# microPower1.net
KiCad netlist of a schematic drawn in Altium Designer
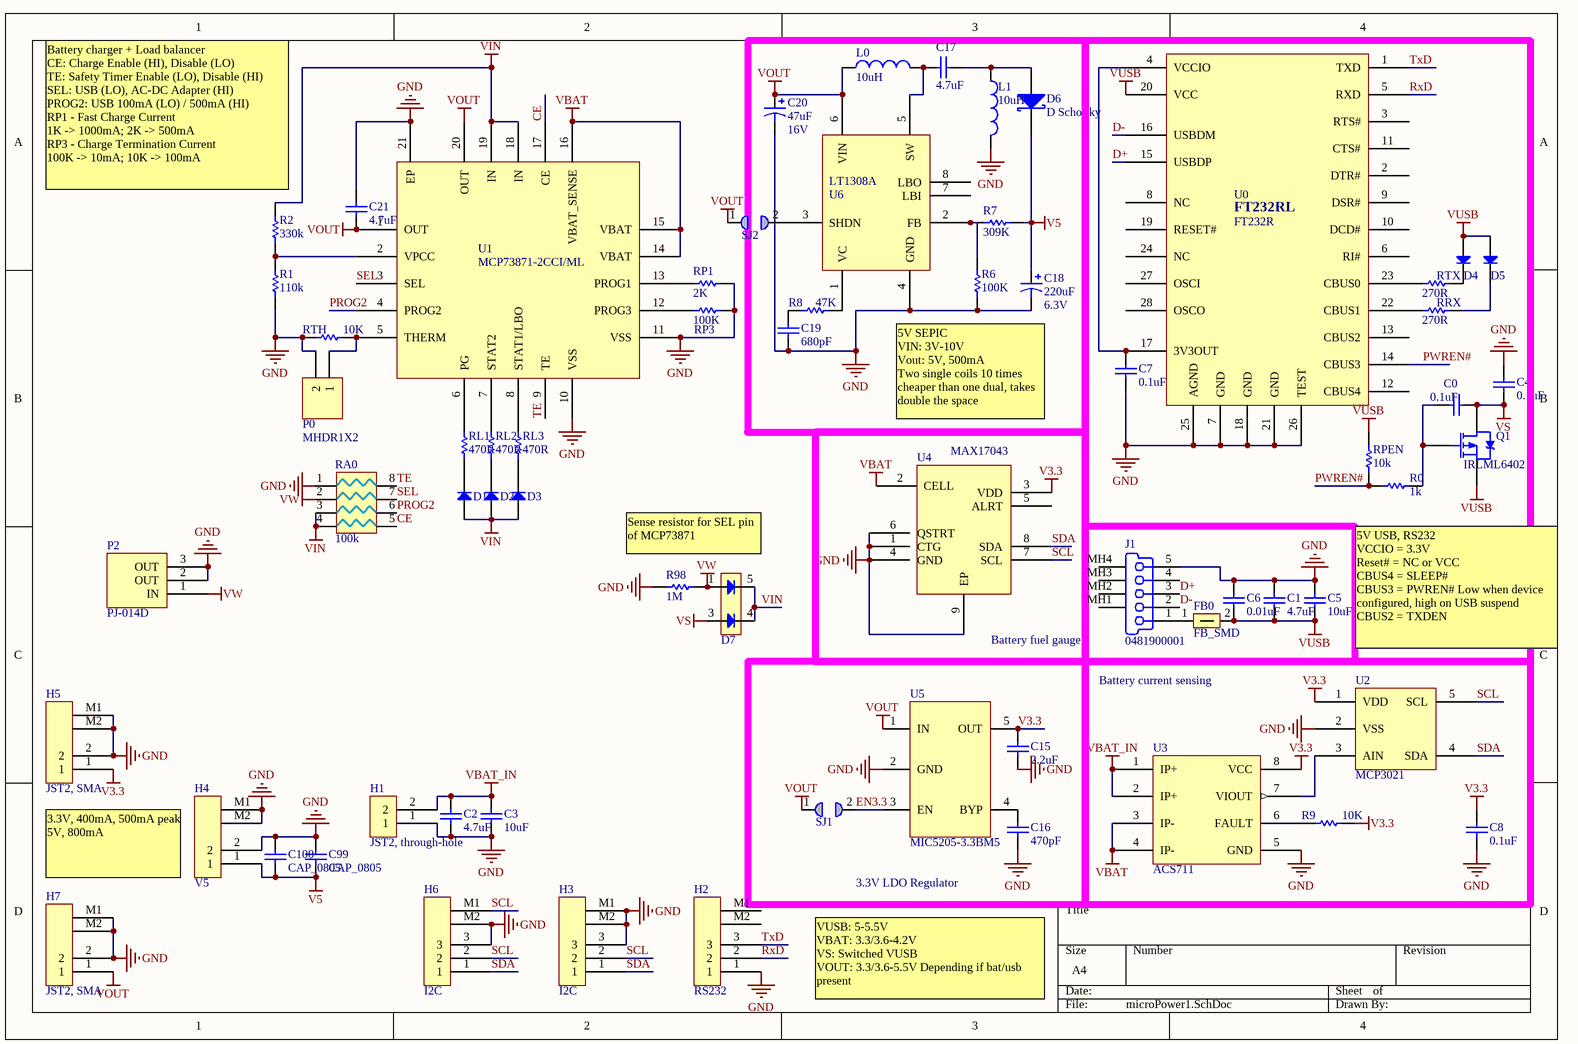
[diagram p0: microPower1.SchDoc]

(export (version "E")
  (design (tool "Eeschema 10.0.6"))
  (components
    (comp (ref "C0")
      (value "0.1uF")
      (footprint "0603_CAP")
      (description "CAP_0603")
      (libsource (lib "ailabLib") (part "CAP_SMD"))
    )
    (comp (ref "C1")
      (value "4.7uF")
      (footprint "0805_CAP")
      (description "Chip Capacitor")
      (libsource (lib "ailabLib") (part "CAP_SMD"))
    )
    (comp (ref "C2")
      (value "4.7uF")
      (footprint "0805_CAP")
      (description "Chip Capacitor")
      (libsource (lib "ailabLib") (part "CAP_SMD"))
    )
    (comp (ref "C3")
      (value "10uF")
      (footprint "0805_CAP")
      (description "Chip Capacitor")
      (libsource (lib "ailabLib") (part "CAP_SMD"))
    )
    (comp (ref "C4")
      (value "0.1uF")
      (footprint "0603_CAP")
      (description "CAP_0603")
      (libsource (lib "ailabLib") (part "CAP_SMD"))
    )
    (comp (ref "C5")
      (value "10uF")
      (footprint "0805_CAP")
      (description "Chip Capacitor")
      (libsource (lib "ailabLib") (part "CAP_SMD"))
    )
    (comp (ref "C6")
      (value "0.01uF")
      (footprint "0603_CAP")
      (description "CAP_0603")
      (libsource (lib "ailabLib") (part "CAP_SMD"))
    )
    (comp (ref "C7")
      (value "0.1uF")
      (footprint "0603_CAP")
      (description "CAP_0603")
      (libsource (lib "ailabLib") (part "CAP_SMD"))
    )
    (comp (ref "C8")
      (value "0.1uF")
      (footprint "0603_CAP")
      (description "CAP_0603")
      (libsource (lib "ailabLib") (part "CAP_SMD"))
    )
    (comp (ref "C15")
      (value "2.2uF")
      (footprint "0603_CAP")
      (description "CAP_0603")
      (libsource (lib "ailabLib") (part "CAP_SMD"))
    )
    (comp (ref "C16")
      (value "470pF")
      (footprint "0603_CAP")
      (description "CAP_0603")
      (libsource (lib "ailabLib") (part "CAP_SMD"))
    )
    (comp (ref "C17")
      (value "4.7uF")
      (footprint "0805_CAP")
      (description "Chip Capacitor")
      (libsource (lib "ailabLib") (part "CAP_SMD"))
    )
    (comp (ref "C18")
      (value "220uF")
      (footprint "CAPMP3528X21N")
      (description "CAP TANT 220UF 6.3V 20% 1411")
      (fields (field (name "VOLTAGE") "6.3V"))
      (libsource (lib "ailabLib") (part "T520B227M006ATE070"))
    )
    (comp (ref "C19")
      (value "680pF")
      (footprint "0603_CAP")
      (description "CAP_0603")
      (libsource (lib "ailabLib") (part "CAP_SMD"))
    )
    (comp (ref "C20")
      (value "47uF")
      (footprint "CAPMP6032X28N")
      (description "CAP TANT 47UF 16V 10% 2312")
      (fields (field (name "VOLTAGE") "16V"))
      (libsource (lib "ailabLib") (part "TR3C476K016C0300"))
    )
    (comp (ref "C21")
      (value "4.7uF")
      (footprint "0805_CAP")
      (description "Chip Capacitor")
      (libsource (lib "ailabLib") (part "CAP_SMD"))
    )
    (comp (ref "C99")
      (value "CAP_0805")
      (footprint "CAP_0805")
      (libsource (lib "ailabLib") (part "CAP_0805"))
    )
    (comp (ref "C100")
      (value "CAP_0805")
      (footprint "CAP_0805")
      (libsource (lib "ailabLib") (part "CAP_0805"))
    )
    (comp (ref "D1") (value "~") (footprint "0603_LED") (libsource (lib "ailabLib") (part "LED_SMD")))
    (comp (ref "D2") (value "~") (footprint "0603_LED") (libsource (lib "ailabLib") (part "LED_SMD")))
    (comp (ref "D3") (value "~") (footprint "0603_LED") (libsource (lib "ailabLib") (part "LED_SMD")))
    (comp (ref "D4") (value "~") (footprint "0603_LED") (libsource (lib "ailabLib") (part "LED_SMD")))
    (comp (ref "D5") (value "~") (footprint "0603_LED") (libsource (lib "ailabLib") (part "LED_SMD")))
    (comp (ref "D6")
      (value "D Schottky")
      (footprint "SMB")
      (description "Schottky Diode")
      (fields (field (name "PUBLISHER") "Altium Limited"))
      (libsource (lib "Miscellaneous Devices") (part "D Schottky"))
    )
    (comp (ref "D7")
      (value "RB496EA")
      (footprint "SOT23-5")
      (description "Schottky barrier diode, 400mV @ 1A")
      (libsource (lib "ailabLib") (part "RB496EA"))
    )
    (comp (ref "FB0") (value "FB_SMD") (footprint "0603_IND") (libsource (lib "ailabLib") (part "FB_SMD")))
    (comp (ref "H1")
      (value "JST2, through-hole")
      (footprint "JST B2B-PH-KL")
      (libsource (lib "ailabLib") (part "JST2, through-hole"))
    )
    (comp (ref "H2")
      (value "RS232")
      (footprint "JST SHR-3V-S")
      (libsource (lib "ailabLib") (part "JST3, SMA"))
    )
    (comp (ref "H3") (value "I2C") (footprint "JST SHR-3V-S") (libsource (lib "ailabLib") (part "JST3, SMA")))
    (comp (ref "H4") (value "V5") (footprint "JST SHR-2V-S") (libsource (lib "ailabLib") (part "JST2, SMA")))
    (comp (ref "H5")
      (value "JST2, SMA")
      (footprint "JST SHR-2V-S")
      (libsource (lib "ailabLib") (part "JST2, SMA"))
    )
    (comp (ref "H6") (value "I2C") (footprint "JST SHR-3V-S") (libsource (lib "ailabLib") (part "JST3, SMA")))
    (comp (ref "H7")
      (value "JST2, SMA")
      (footprint "JST SHR-2V-S")
      (libsource (lib "ailabLib") (part "JST2, SMA"))
    )
    (comp (ref "J1")
      (value "0481900001")
      (footprint "481900001")
      (fields (field (name "PUBLISHER") "Altium Limited"))
      (libsource (lib "ailabLib") (part "0481900001"))
    )
    (comp (ref "L0")
      (value "10uH")
      (footprint "INDP6060X45L")
      (description "INDUCTOR 10UH 3A 20% SMD")
      (libsource (lib "ailabLib") (part "NR6045T100M"))
    )
    (comp (ref "L1")
      (value "10uH")
      (footprint "INDP6060X45L")
      (description "INDUCTOR 10UH 3A 20% SMD")
      (libsource (lib "ailabLib") (part "NR6045T100M"))
    )
    (comp (ref "P0")
      (value "MHDR1X2")
      (footprint "MHDR1X2")
      (description "Header, 2-Pin")
      (fields (field (name "PUBLISHER") "Altium Limited"))
      (libsource (lib "Miscellaneous Connectors") (part "MHDR1X2"))
    )
    (comp (ref "P2")
      (value "PJ-014D")
      (footprint "PJ-014D")
      (description "Power jack, 4.2mm OD, 1.3mm ID, through-hole")
      (libsource (lib "ailabLib") (part "PJ-014D"))
    )
    (comp (ref "Q1")
      (value "IRLML6402")
      (footprint "Micro3_N")
      (description "HEXFET Power MOSFET")
      (fields (field (name "PUBLISHER") "Altium Limited"))
      (libsource (lib "IR Discrete MOSFET - Power") (part "IRLML6401"))
    )
    (comp (ref "R0") (value "1k") (footprint "0603_RES") (libsource (lib "ailabLib") (part "RES_SMD")))
    (comp (ref "R1") (value "110k") (footprint "0603_RES") (libsource (lib "ailabLib") (part "RES_SMD")))
    (comp (ref "R2") (value "330k") (footprint "0603_RES") (libsource (lib "ailabLib") (part "RES_SMD")))
    (comp (ref "R6") (value "100K") (footprint "0603_RES") (libsource (lib "ailabLib") (part "RES_SMD")))
    (comp (ref "R7") (value "309K") (footprint "0603_RES") (libsource (lib "ailabLib") (part "RES_SMD")))
    (comp (ref "R8") (value "47K") (footprint "0603_RES") (libsource (lib "ailabLib") (part "RES_SMD")))
    (comp (ref "R9") (value "10K") (footprint "0603_RES") (libsource (lib "ailabLib") (part "RES_SMD")))
    (comp (ref "R98") (value "1M") (footprint "0603_RES") (libsource (lib "ailabLib") (part "RES_SMD")))
    (comp (ref "RA0")
      (value "100k")
      (footprint "RESCAXS80P320X150X60-8N")
      (description "Resistor array, 4-Way, SMD")
      (libsource (lib "ailabLib") (part "RES_ARR4"))
    )
    (comp (ref "RL1") (value "470R") (footprint "0603_RES") (libsource (lib "ailabLib") (part "RES_SMD")))
    (comp (ref "RL2") (value "470R") (footprint "0603_RES") (libsource (lib "ailabLib") (part "RES_SMD")))
    (comp (ref "RL3") (value "470R") (footprint "0603_RES") (libsource (lib "ailabLib") (part "RES_SMD")))
    (comp (ref "RP1") (value "2K") (footprint "0603_RES") (libsource (lib "ailabLib") (part "RES_SMD")))
    (comp (ref "RP3") (value "100K") (footprint "0603_RES") (libsource (lib "ailabLib") (part "RES_SMD")))
    (comp (ref "RPEN") (value "10k") (footprint "0603_RES") (libsource (lib "ailabLib") (part "RES_SMD")))
    (comp (ref "RRX") (value "270R") (footprint "0603_RES") (libsource (lib "ailabLib") (part "RES_SMD")))
    (comp (ref "RTH") (value "10K") (footprint "0603_RES") (libsource (lib "ailabLib") (part "RES_SMD")))
    (comp (ref "RTX") (value "270R") (footprint "0603_RES") (libsource (lib "ailabLib") (part "RES_SMD")))
    (comp (ref "SJ1")
      (value "SJ")
      (footprint "0603_SJ")
      (description "Solder Joint")
      (libsource (lib "ailabLib") (part "SJ"))
    )
    (comp (ref "SJ2")
      (value "SJ")
      (footprint "0603_SJ")
      (description "Solder Joint")
      (libsource (lib "ailabLib") (part "SJ"))
    )
    (comp (ref "U0")
      (value "FT232R")
      (footprint "SOP65P780X200-28N")
      (libsource (lib "ailabLib") (part "FT232R"))
    )
    (comp (ref "U1")
      (value "MCP73871-2CCI/ML")
      (footprint "MCP73871-2CCI/ML")
      (libsource (lib "ailabLib") (part "MCP73871-2CCI/ML"))
    )
    (comp (ref "U2") (value "MCP3021") (footprint "SOT23-5") (libsource (lib "ailabLib") (part "MCP3021")))
    (comp (ref "U3")
      (value "ACS711")
      (footprint "SOP127P600X175-8M")
      (libsource (lib "ailabLib") (part "ACS711"))
    )
    (comp (ref "U4")
      (value "MAX17043")
      (footprint "QFN50P300X200X80-8N")
      (description "Compact, Low-Cost 1S/2S Fuel Gauges with Low-Battery Alert")
      (libsource (lib "ailabLib") (part "MAX17043"))
    )
    (comp (ref "U5")
      (value "MIC5205-3.3BM5")
      (footprint "SOT95P280X130-5N")
      (description "Micrel MIC5205 LDO Voltage Regulator")
      (libsource (lib "ailabLib") (part "MIC5205"))
    )
    (comp (ref "U6")
      (value "LT1308A")
      (footprint "SOP127P600X175-8N")
      (description "High Current, Micropower Single Cell, 600kHz  DC/DC Converters")
      (libsource (lib "ailabLib") (part "LT1308"))
    )
  )
  (nets
    (net (code "1") (name "/CE") (class "Default")
      (node (ref "RA0") (pin "5") (pinfunction "5_5") (pintype "passive"))
      (node (ref "U1") (pin "17") (pinfunction "CE_17") (pintype "passive"))
    )
    (net (code "2") (name "/D+") (class "Default")
      (node (ref "J1") (pin "3") (pinfunction "D+_3") (pintype "passive"))
      (node (ref "U0") (pin "15") (pinfunction "USBDP_15") (pintype "passive"))
    )
    (net (code "3") (name "/D-") (class "Default")
      (node (ref "J1") (pin "2") (pinfunction "D-_2") (pintype "passive"))
      (node (ref "U0") (pin "16") (pinfunction "USBDM_16") (pintype "passive"))
    )
    (net (code "4") (name "/EN3.3") (class "Default")
      (node (ref "SJ1") (pin "2") (pintype "passive"))
      (node (ref "U5") (pin "3") (pinfunction "EN_3") (pintype "power_in"))
    )
    (net (code "5") (name "/PROG2") (class "Default")
      (node (ref "RA0") (pin "6") (pinfunction "6_6") (pintype "passive"))
      (node (ref "U1") (pin "4") (pinfunction "PROG2_4") (pintype "passive"))
    )
    (net (code "6") (name "/PWREN#") (class "Default")
      (node (ref "R0") (pin "1") (pinfunction "1_1") (pintype "passive"))
      (node (ref "RPEN") (pin "2") (pinfunction "2_2") (pintype "passive"))
      (node (ref "U0") (pin "14") (pinfunction "CBUS3_14") (pintype "passive"))
    )
    (net (code "7") (name "/RxD") (class "Default")
      (node (ref "H2") (pin "2") (pinfunction "2_2") (pintype "passive"))
      (node (ref "U0") (pin "5") (pinfunction "RXD_5") (pintype "passive"))
    )
    (net (code "8") (name "/SCL") (class "Default")
      (node (ref "H3") (pin "2") (pinfunction "2_2") (pintype "passive"))
      (node (ref "H6") (pin "2") (pinfunction "2_2") (pintype "passive"))
      (node (ref "H6") (pin "M1") (pinfunction "M1_M1") (pintype "passive"))
      (node (ref "U2") (pin "5") (pinfunction "SCL_5") (pintype "passive"))
      (node (ref "U4") (pin "7") (pinfunction "SCL_7") (pintype "passive"))
    )
    (net (code "9") (name "/SDA") (class "Default")
      (node (ref "H3") (pin "1") (pinfunction "1_1") (pintype "passive"))
      (node (ref "H6") (pin "1") (pinfunction "1_1") (pintype "passive"))
      (node (ref "U2") (pin "4") (pinfunction "SDA_4") (pintype "passive"))
      (node (ref "U4") (pin "8") (pinfunction "SDA_8") (pintype "passive"))
    )
    (net (code "10") (name "/SEL") (class "Default")
      (node (ref "RA0") (pin "7") (pinfunction "7_7") (pintype "passive"))
      (node (ref "U1") (pin "3") (pinfunction "SEL_3") (pintype "passive"))
    )
    (net (code "11") (name "/TE") (class "Default")
      (node (ref "RA0") (pin "8") (pinfunction "8_8") (pintype "passive"))
      (node (ref "U1") (pin "9") (pinfunction "TE_9") (pintype "passive"))
    )
    (net (code "12") (name "/TxD") (class "Default")
      (node (ref "H2") (pin "3") (pinfunction "3_3") (pintype "passive"))
      (node (ref "U0") (pin "1") (pinfunction "TXD_1") (pintype "passive"))
    )
    (net (code "13") (name "GND") (class "Default")
      (node (ref "C1") (pin "2") (pinfunction "2_2") (pintype "passive"))
      (node (ref "C100") (pin "1") (pinfunction "1_1") (pintype "passive"))
      (node (ref "C15") (pin "2") (pinfunction "2_2") (pintype "passive"))
      (node (ref "C16") (pin "2") (pinfunction "2_2") (pintype "passive"))
      (node (ref "C18") (pin "2") (pinfunction "2_2") (pintype "passive"))
      (node (ref "C19") (pin "2") (pinfunction "2_2") (pintype "passive"))
      (node (ref "C2") (pin "1") (pinfunction "1_1") (pintype "passive"))
      (node (ref "C20") (pin "2") (pinfunction "2_2") (pintype "passive"))
      (node (ref "C21") (pin "2") (pinfunction "2_2") (pintype "passive"))
      (node (ref "C3") (pin "1") (pinfunction "1_1") (pintype "passive"))
      (node (ref "C4") (pin "1") (pinfunction "1_1") (pintype "passive"))
      (node (ref "C5") (pin "2") (pinfunction "2_2") (pintype "passive"))
      (node (ref "C6") (pin "2") (pinfunction "2_2") (pintype "passive"))
      (node (ref "C7") (pin "1") (pinfunction "1_1") (pintype "passive"))
      (node (ref "C8") (pin "1") (pinfunction "1_1") (pintype "passive"))
      (node (ref "C99") (pin "1") (pinfunction "1_1") (pintype "passive"))
      (node (ref "H1") (pin "1") (pinfunction "1_1") (pintype "passive"))
      (node (ref "H2") (pin "1") (pinfunction "1_1") (pintype "passive"))
      (node (ref "H3") (pin "3") (pinfunction "3_3") (pintype "passive"))
      (node (ref "H3") (pin "M1") (pinfunction "M1_M1") (pintype "passive"))
      (node (ref "H3") (pin "M2") (pinfunction "M2_M2") (pintype "passive"))
      (node (ref "H4") (pin "2") (pinfunction "2_2") (pintype "passive"))
      (node (ref "H4") (pin "M1") (pinfunction "M1_M1") (pintype "passive"))
      (node (ref "H4") (pin "M2") (pinfunction "M2_M2") (pintype "passive"))
      (node (ref "H5") (pin "2") (pinfunction "2_2") (pintype "passive"))
      (node (ref "H5") (pin "M1") (pinfunction "M1_M1") (pintype "passive"))
      (node (ref "H5") (pin "M2") (pinfunction "M2_M2") (pintype "passive"))
      (node (ref "H6") (pin "3") (pinfunction "3_3") (pintype "passive"))
      (node (ref "H6") (pin "M2") (pinfunction "M2_M2") (pintype "passive"))
      (node (ref "H7") (pin "2") (pinfunction "2_2") (pintype "passive"))
      (node (ref "H7") (pin "M1") (pinfunction "M1_M1") (pintype "passive"))
      (node (ref "H7") (pin "M2") (pinfunction "M2_M2") (pintype "passive"))
      (node (ref "J1") (pin "5") (pinfunction "GND_5") (pintype "passive"))
      (node (ref "L1") (pin "2") (pinfunction "2_2") (pintype "passive"))
      (node (ref "P0") (pin "2") (pinfunction "2_2") (pintype "passive"))
      (node (ref "P2") (pin "2") (pinfunction "OUT_2") (pintype "passive"))
      (node (ref "P2") (pin "3") (pinfunction "OUT_3") (pintype "passive"))
      (node (ref "R1") (pin "1") (pinfunction "1_1") (pintype "passive"))
      (node (ref "R6") (pin "1") (pinfunction "1_1") (pintype "passive"))
      (node (ref "R98") (pin "2") (pinfunction "2_2") (pintype "passive"))
      (node (ref "RA0") (pin "1") (pinfunction "1_1") (pintype "passive"))
      (node (ref "RP1") (pin "2") (pinfunction "2_2") (pintype "passive"))
      (node (ref "RP3") (pin "2") (pinfunction "2_2") (pintype "passive"))
      (node (ref "RTH") (pin "1") (pinfunction "1_1") (pintype "passive"))
      (node (ref "U0") (pin "18") (pinfunction "GND_18") (pintype "passive"))
      (node (ref "U0") (pin "21") (pinfunction "GND_21") (pintype "passive"))
      (node (ref "U0") (pin "25") (pinfunction "AGND_25") (pintype "passive"))
      (node (ref "U0") (pin "26") (pinfunction "TEST_26") (pintype "passive"))
      (node (ref "U0") (pin "7") (pinfunction "GND_7") (pintype "passive"))
      (node (ref "U1") (pin "10") (pinfunction "VSS_10") (pintype "passive"))
      (node (ref "U1") (pin "11") (pinfunction "VSS_11") (pintype "passive"))
      (node (ref "U1") (pin "21") (pinfunction "EP_21") (pintype "passive"))
      (node (ref "U2") (pin "2") (pinfunction "VSS_2") (pintype "passive"))
      (node (ref "U3") (pin "5") (pinfunction "GND_5") (pintype "power_in"))
      (node (ref "U4") (pin "1") (pinfunction "CTG_1") (pintype "passive"))
      (node (ref "U4") (pin "4") (pinfunction "GND_4") (pintype "passive"))
      (node (ref "U4") (pin "6") (pinfunction "QSTRT_6") (pintype "passive"))
      (node (ref "U4") (pin "9") (pinfunction "EP_9") (pintype "passive"))
      (node (ref "U5") (pin "2") (pinfunction "GND_2") (pintype "power_in"))
      (node (ref "U6") (pin "4") (pinfunction "GND_4") (pintype "passive"))
    )
    (net (code "14") (name "Net-(C19-Pad1)") (class "Default")
      (node (ref "C19") (pin "1") (pinfunction "1_1") (pintype "passive"))
      (node (ref "R8") (pin "2") (pinfunction "2_2") (pintype "passive"))
    )
    (net (code "15") (name "Net-(D1-K)") (class "Default")
      (node (ref "D1") (pin "2") (pinfunction "K_2") (pintype "passive"))
      (node (ref "RL1") (pin "1") (pinfunction "1_1") (pintype "passive"))
    )
    (net (code "16") (name "Net-(D2-K)") (class "Default")
      (node (ref "D2") (pin "2") (pinfunction "K_2") (pintype "passive"))
      (node (ref "RL2") (pin "1") (pinfunction "1_1") (pintype "passive"))
    )
    (net (code "17") (name "Net-(D3-K)") (class "Default")
      (node (ref "D3") (pin "2") (pinfunction "K_2") (pintype "passive"))
      (node (ref "RL3") (pin "1") (pinfunction "1_1") (pintype "passive"))
    )
    (net (code "18") (name "Net-(D4-K)") (class "Default")
      (node (ref "D4") (pin "2") (pinfunction "K_2") (pintype "passive"))
      (node (ref "RTX") (pin "1") (pinfunction "1_1") (pintype "passive"))
    )
    (net (code "19") (name "Net-(D5-K)") (class "Default")
      (node (ref "D5") (pin "2") (pinfunction "K_2") (pintype "passive"))
      (node (ref "RRX") (pin "1") (pinfunction "1_1") (pintype "passive"))
    )
    (net (code "20") (name "Net-(D6-A)") (class "Default")
      (node (ref "C17") (pin "2") (pinfunction "2_2") (pintype "passive"))
      (node (ref "D6") (pin "1") (pinfunction "A_1") (pintype "passive"))
      (node (ref "L1") (pin "1") (pinfunction "1_1") (pintype "passive"))
    )
    (net (code "21") (name "Net-(J1-V_BUS_(5V))") (class "Default")
      (node (ref "FB0") (pin "1") (pinfunction "1_1") (pintype "passive"))
      (node (ref "J1") (pin "1") (pinfunction "V_BUS_(5V)_1") (pintype "passive"))
    )
    (net (code "22") (name "Net-(Q1-G)") (class "Default")
      (node (ref "C0") (pin "1") (pinfunction "1_1") (pintype "passive"))
      (node (ref "Q1") (pin "1") (pinfunction "G_1") (pintype "passive"))
      (node (ref "R0") (pin "2") (pinfunction "2_2") (pintype "passive"))
    )
    (net (code "23") (name "Net-(U0-3V3OUT)") (class "Default")
      (node (ref "C7") (pin "2") (pinfunction "2_2") (pintype "passive"))
      (node (ref "U0") (pin "17") (pinfunction "3V3OUT_17") (pintype "passive"))
      (node (ref "U0") (pin "4") (pinfunction "VCCIO_4") (pintype "passive"))
    )
    (net (code "24") (name "Net-(U0-CBUS0)") (class "Default")
      (node (ref "RTX") (pin "2") (pinfunction "2_2") (pintype "passive"))
      (node (ref "U0") (pin "23") (pinfunction "CBUS0_23") (pintype "passive"))
    )
    (net (code "25") (name "Net-(U0-CBUS1)") (class "Default")
      (node (ref "RRX") (pin "2") (pinfunction "2_2") (pintype "passive"))
      (node (ref "U0") (pin "22") (pinfunction "CBUS1_22") (pintype "passive"))
    )
    (net (code "26") (name "Net-(U1-PG)") (class "Default")
      (node (ref "RL1") (pin "2") (pinfunction "2_2") (pintype "passive"))
      (node (ref "U1") (pin "6") (pinfunction "PG_6") (pintype "passive"))
    )
    (net (code "27") (name "Net-(U1-PROG1)") (class "Default")
      (node (ref "RP1") (pin "1") (pinfunction "1_1") (pintype "passive"))
      (node (ref "U1") (pin "13") (pinfunction "PROG1_13") (pintype "passive"))
    )
    (net (code "28") (name "Net-(U1-PROG3)") (class "Default")
      (node (ref "RP3") (pin "1") (pinfunction "1_1") (pintype "passive"))
      (node (ref "U1") (pin "12") (pinfunction "PROG3_12") (pintype "passive"))
    )
    (net (code "29") (name "Net-(U1-STAT1{slash}LBO)") (class "Default")
      (node (ref "RL3") (pin "2") (pinfunction "2_2") (pintype "passive"))
      (node (ref "U1") (pin "8") (pinfunction "STAT1/LBO_8") (pintype "passive"))
    )
    (net (code "30") (name "Net-(U1-STAT2)") (class "Default")
      (node (ref "RL2") (pin "2") (pinfunction "2_2") (pintype "passive"))
      (node (ref "U1") (pin "7") (pinfunction "STAT2_7") (pintype "passive"))
    )
    (net (code "31") (name "Net-(U1-THERM)") (class "Default")
      (node (ref "P0") (pin "1") (pinfunction "1_1") (pintype "passive"))
      (node (ref "RTH") (pin "2") (pinfunction "2_2") (pintype "passive"))
      (node (ref "U1") (pin "5") (pinfunction "THERM_5") (pintype "passive"))
    )
    (net (code "32") (name "Net-(U1-VPCC)") (class "Default")
      (node (ref "R1") (pin "2") (pinfunction "2_2") (pintype "passive"))
      (node (ref "R2") (pin "2") (pinfunction "2_2") (pintype "passive"))
      (node (ref "U1") (pin "2") (pinfunction "VPCC_2") (pintype "passive"))
    )
    (net (code "33") (name "Net-(U2-AIN)") (class "Default")
      (node (ref "U2") (pin "3") (pinfunction "AIN_3") (pintype "passive"))
      (node (ref "U3") (pin "7") (pinfunction "VIOUT_7") (pintype "output"))
    )
    (net (code "34") (name "Net-(U3-FAULT)") (class "Default")
      (node (ref "R9") (pin "1") (pinfunction "1_1") (pintype "passive"))
      (node (ref "U3") (pin "6") (pinfunction "FAULT_6") (pintype "passive"))
    )
    (net (code "35") (name "Net-(U5-BYP)") (class "Default")
      (node (ref "C16") (pin "1") (pinfunction "1_1") (pintype "passive"))
      (node (ref "U5") (pin "4") (pinfunction "BYP_4") (pintype "power_in"))
    )
    (net (code "36") (name "Net-(U6-FB)") (class "Default")
      (node (ref "R6") (pin "2") (pinfunction "2_2") (pintype "passive"))
      (node (ref "R7") (pin "2") (pinfunction "2_2") (pintype "passive"))
      (node (ref "U6") (pin "2") (pinfunction "FB_2") (pintype "passive"))
    )
    (net (code "37") (name "Net-(U6-SHDN)") (class "Default")
      (node (ref "SJ2") (pin "2") (pintype "passive"))
      (node (ref "U6") (pin "3") (pinfunction "SHDN_3") (pintype "passive"))
    )
    (net (code "38") (name "Net-(U6-SW)") (class "Default")
      (node (ref "C17") (pin "1") (pinfunction "1_1") (pintype "passive"))
      (node (ref "L0") (pin "2") (pinfunction "2_2") (pintype "passive"))
      (node (ref "U6") (pin "5") (pinfunction "SW_5") (pintype "passive"))
    )
    (net (code "39") (name "Net-(U6-VC)") (class "Default")
      (node (ref "R8") (pin "1") (pinfunction "1_1") (pintype "passive"))
      (node (ref "U6") (pin "1") (pinfunction "VC_1") (pintype "passive"))
    )
    (net (code "40") (name "V3.3") (class "Default")
      (node (ref "C15") (pin "1") (pinfunction "1_1") (pintype "passive"))
      (node (ref "C8") (pin "2") (pinfunction "2_2") (pintype "passive"))
      (node (ref "H5") (pin "1") (pinfunction "1_1") (pintype "passive"))
      (node (ref "R9") (pin "2") (pinfunction "2_2") (pintype "passive"))
      (node (ref "U2") (pin "1") (pinfunction "VDD_1") (pintype "passive"))
      (node (ref "U3") (pin "8") (pinfunction "VCC_8") (pintype "power_in"))
      (node (ref "U4") (pin "3") (pinfunction "VDD_3") (pintype "passive"))
      (node (ref "U5") (pin "5") (pinfunction "OUT_5") (pintype "power_in"))
    )
    (net (code "41") (name "V5") (class "Default")
      (node (ref "C100") (pin "2") (pinfunction "2_2") (pintype "passive"))
      (node (ref "C18") (pin "1") (pinfunction "1_1") (pintype "passive"))
      (node (ref "C99") (pin "2") (pinfunction "2_2") (pintype "passive"))
      (node (ref "D6") (pin "2") (pinfunction "K_2") (pintype "passive"))
      (node (ref "H4") (pin "1") (pinfunction "1_1") (pintype "passive"))
      (node (ref "R7") (pin "1") (pinfunction "1_1") (pintype "passive"))
    )
    (net (code "42") (name "VBAT") (class "Default")
      (node (ref "U1") (pin "14") (pinfunction "VBAT_14") (pintype "passive"))
      (node (ref "U1") (pin "15") (pinfunction "VBAT_15") (pintype "passive"))
      (node (ref "U1") (pin "16") (pinfunction "VBAT_SENSE_16") (pintype "passive"))
      (node (ref "U3") (pin "3") (pinfunction "IP-_3") (pintype "passive"))
      (node (ref "U3") (pin "4") (pinfunction "IP-_4") (pintype "passive"))
      (node (ref "U4") (pin "2") (pinfunction "CELL_2") (pintype "passive"))
    )
    (net (code "43") (name "VBAT_IN") (class "Default")
      (node (ref "C2") (pin "2") (pinfunction "2_2") (pintype "passive"))
      (node (ref "C3") (pin "2") (pinfunction "2_2") (pintype "passive"))
      (node (ref "H1") (pin "2") (pinfunction "2_2") (pintype "passive"))
      (node (ref "U3") (pin "1") (pinfunction "IP+_1") (pintype "passive"))
      (node (ref "U3") (pin "2") (pinfunction "IP+_2") (pintype "passive"))
    )
    (net (code "44") (name "VIN") (class "Default")
      (node (ref "D1") (pin "1") (pinfunction "A_1") (pintype "passive"))
      (node (ref "D2") (pin "1") (pinfunction "A_1") (pintype "passive"))
      (node (ref "D3") (pin "1") (pinfunction "A_1") (pintype "passive"))
      (node (ref "D7") (pin "4") (pinfunction "4_4") (pintype "passive"))
      (node (ref "D7") (pin "5") (pinfunction "5_5") (pintype "passive"))
      (node (ref "R2") (pin "1") (pinfunction "1_1") (pintype "passive"))
      (node (ref "RA0") (pin "3") (pinfunction "3_3") (pintype "passive"))
      (node (ref "RA0") (pin "4") (pinfunction "4_4") (pintype "passive"))
      (node (ref "U1") (pin "18") (pinfunction "IN_18") (pintype "passive"))
      (node (ref "U1") (pin "19") (pinfunction "IN_19") (pintype "passive"))
    )
    (net (code "45") (name "VOUT") (class "Default")
      (node (ref "C20") (pin "1") (pinfunction "1_1") (pintype "passive"))
      (node (ref "C21") (pin "1") (pinfunction "1_1") (pintype "passive"))
      (node (ref "H7") (pin "1") (pinfunction "1_1") (pintype "passive"))
      (node (ref "L0") (pin "1") (pinfunction "1_1") (pintype "passive"))
      (node (ref "SJ1") (pin "1") (pintype "passive"))
      (node (ref "SJ2") (pin "1") (pintype "passive"))
      (node (ref "U1") (pin "1") (pinfunction "OUT_1") (pintype "passive"))
      (node (ref "U1") (pin "20") (pinfunction "OUT_20") (pintype "passive"))
      (node (ref "U5") (pin "1") (pinfunction "IN_1") (pintype "power_in"))
      (node (ref "U6") (pin "6") (pinfunction "VIN_6") (pintype "passive"))
    )
    (net (code "46") (name "VS") (class "Default")
      (node (ref "C0") (pin "2") (pinfunction "2_2") (pintype "passive"))
      (node (ref "C4") (pin "2") (pinfunction "2_2") (pintype "passive"))
      (node (ref "D7") (pin "3") (pinfunction "3_3") (pintype "passive"))
      (node (ref "Q1") (pin "3") (pinfunction "D_3") (pintype "passive"))
    )
    (net (code "47") (name "VUSB") (class "Default")
      (node (ref "C1") (pin "1") (pinfunction "1_1") (pintype "passive"))
      (node (ref "C5") (pin "1") (pinfunction "1_1") (pintype "passive"))
      (node (ref "C6") (pin "1") (pinfunction "1_1") (pintype "passive"))
      (node (ref "D4") (pin "1") (pinfunction "A_1") (pintype "passive"))
      (node (ref "D5") (pin "1") (pinfunction "A_1") (pintype "passive"))
      (node (ref "FB0") (pin "2") (pinfunction "2_2") (pintype "passive"))
      (node (ref "Q1") (pin "2") (pinfunction "S_2") (pintype "passive"))
      (node (ref "RPEN") (pin "1") (pinfunction "1_1") (pintype "passive"))
      (node (ref "U0") (pin "20") (pinfunction "VCC_20") (pintype "passive"))
    )
    (net (code "48") (name "VW") (class "Default")
      (node (ref "D7") (pin "1") (pinfunction "1_1") (pintype "passive"))
      (node (ref "P2") (pin "1") (pinfunction "IN_1") (pintype "passive"))
      (node (ref "R98") (pin "1") (pinfunction "1_1") (pintype "passive"))
      (node (ref "RA0") (pin "2") (pinfunction "2_2") (pintype "passive"))
    )
    (net (code "49") (name "unconnected-(H2-PadM1)") (class "Default")
      (node (ref "H2") (pin "M1") (pinfunction "M1_M1") (pintype "passive"))
    )
    (net (code "50") (name "unconnected-(H2-PadM2)") (class "Default")
      (node (ref "H2") (pin "M2") (pinfunction "M2_M2") (pintype "passive"))
    )
    (net (code "51") (name "unconnected-(J1-NC-Pad4)") (class "Default")
      (node (ref "J1") (pin "4") (pinfunction "NC_4") (pintype "passive"))
    )
    (net (code "52") (name "unconnected-(J1-Tab-PadMH1)") (class "Default")
      (node (ref "J1") (pin "MH1") (pinfunction "Tab_MH1") (pintype "passive"))
    )
    (net (code "53") (name "unconnected-(J1-Tab-PadMH2)") (class "Default")
      (node (ref "J1") (pin "MH2") (pinfunction "Tab_MH2") (pintype "passive"))
    )
    (net (code "54") (name "unconnected-(J1-Tab-PadMH3)") (class "Default")
      (node (ref "J1") (pin "MH3") (pinfunction "Tab_MH3") (pintype "passive"))
    )
    (net (code "55") (name "unconnected-(J1-Tab-PadMH4)") (class "Default")
      (node (ref "J1") (pin "MH4") (pinfunction "Tab_MH4") (pintype "passive"))
    )
    (net (code "56") (name "unconnected-(U0-CBUS2-Pad13)") (class "Default")
      (node (ref "U0") (pin "13") (pinfunction "CBUS2_13") (pintype "passive"))
    )
    (net (code "57") (name "unconnected-(U0-CBUS4-Pad12)") (class "Default")
      (node (ref "U0") (pin "12") (pinfunction "CBUS4_12") (pintype "passive"))
    )
    (net (code "58") (name "unconnected-(U0-CTS#-Pad11)") (class "Default")
      (node (ref "U0") (pin "11") (pinfunction "CTS#_11") (pintype "passive"))
    )
    (net (code "59") (name "unconnected-(U0-DCD#-Pad10)") (class "Default")
      (node (ref "U0") (pin "10") (pinfunction "DCD#_10") (pintype "passive"))
    )
    (net (code "60") (name "unconnected-(U0-DSR#-Pad9)") (class "Default")
      (node (ref "U0") (pin "9") (pinfunction "DSR#_9") (pintype "passive"))
    )
    (net (code "61") (name "unconnected-(U0-DTR#-Pad2)") (class "Default")
      (node (ref "U0") (pin "2") (pinfunction "DTR#_2") (pintype "passive"))
    )
    (net (code "62") (name "unconnected-(U0-NC-Pad8)") (class "Default")
      (node (ref "U0") (pin "8") (pinfunction "NC_8") (pintype "passive"))
    )
    (net (code "63") (name "unconnected-(U0-NC-Pad24)") (class "Default")
      (node (ref "U0") (pin "24") (pinfunction "NC_24") (pintype "passive"))
    )
    (net (code "64") (name "unconnected-(U0-OSCI-Pad27)") (class "Default")
      (node (ref "U0") (pin "27") (pinfunction "OSCI_27") (pintype "passive"))
    )
    (net (code "65") (name "unconnected-(U0-OSCO-Pad28)") (class "Default")
      (node (ref "U0") (pin "28") (pinfunction "OSCO_28") (pintype "passive"))
    )
    (net (code "66") (name "unconnected-(U0-RESET#-Pad19)") (class "Default")
      (node (ref "U0") (pin "19") (pinfunction "RESET#_19") (pintype "passive"))
    )
    (net (code "67") (name "unconnected-(U0-RI#-Pad6)") (class "Default")
      (node (ref "U0") (pin "6") (pinfunction "RI#_6") (pintype "passive"))
    )
    (net (code "68") (name "unconnected-(U0-RTS#-Pad3)") (class "Default")
      (node (ref "U0") (pin "3") (pinfunction "RTS#_3") (pintype "passive"))
    )
    (net (code "69") (name "unconnected-(U4-ALRT-Pad5)") (class "Default")
      (node (ref "U4") (pin "5") (pinfunction "ALRT_5") (pintype "passive"))
    )
    (net (code "70") (name "unconnected-(U6-LBI-Pad7)") (class "Default")
      (node (ref "U6") (pin "7") (pinfunction "LBI_7") (pintype "passive"))
    )
    (net (code "71") (name "unconnected-(U6-LBO-Pad8)") (class "Default")
      (node (ref "U6") (pin "8") (pinfunction "LBO_8") (pintype "passive"))
    )
  )
)
